# MCH_FPGA_Banks_44_45_46_DDR64.net
KiCad netlist of a schematic drawn in Altium Designer
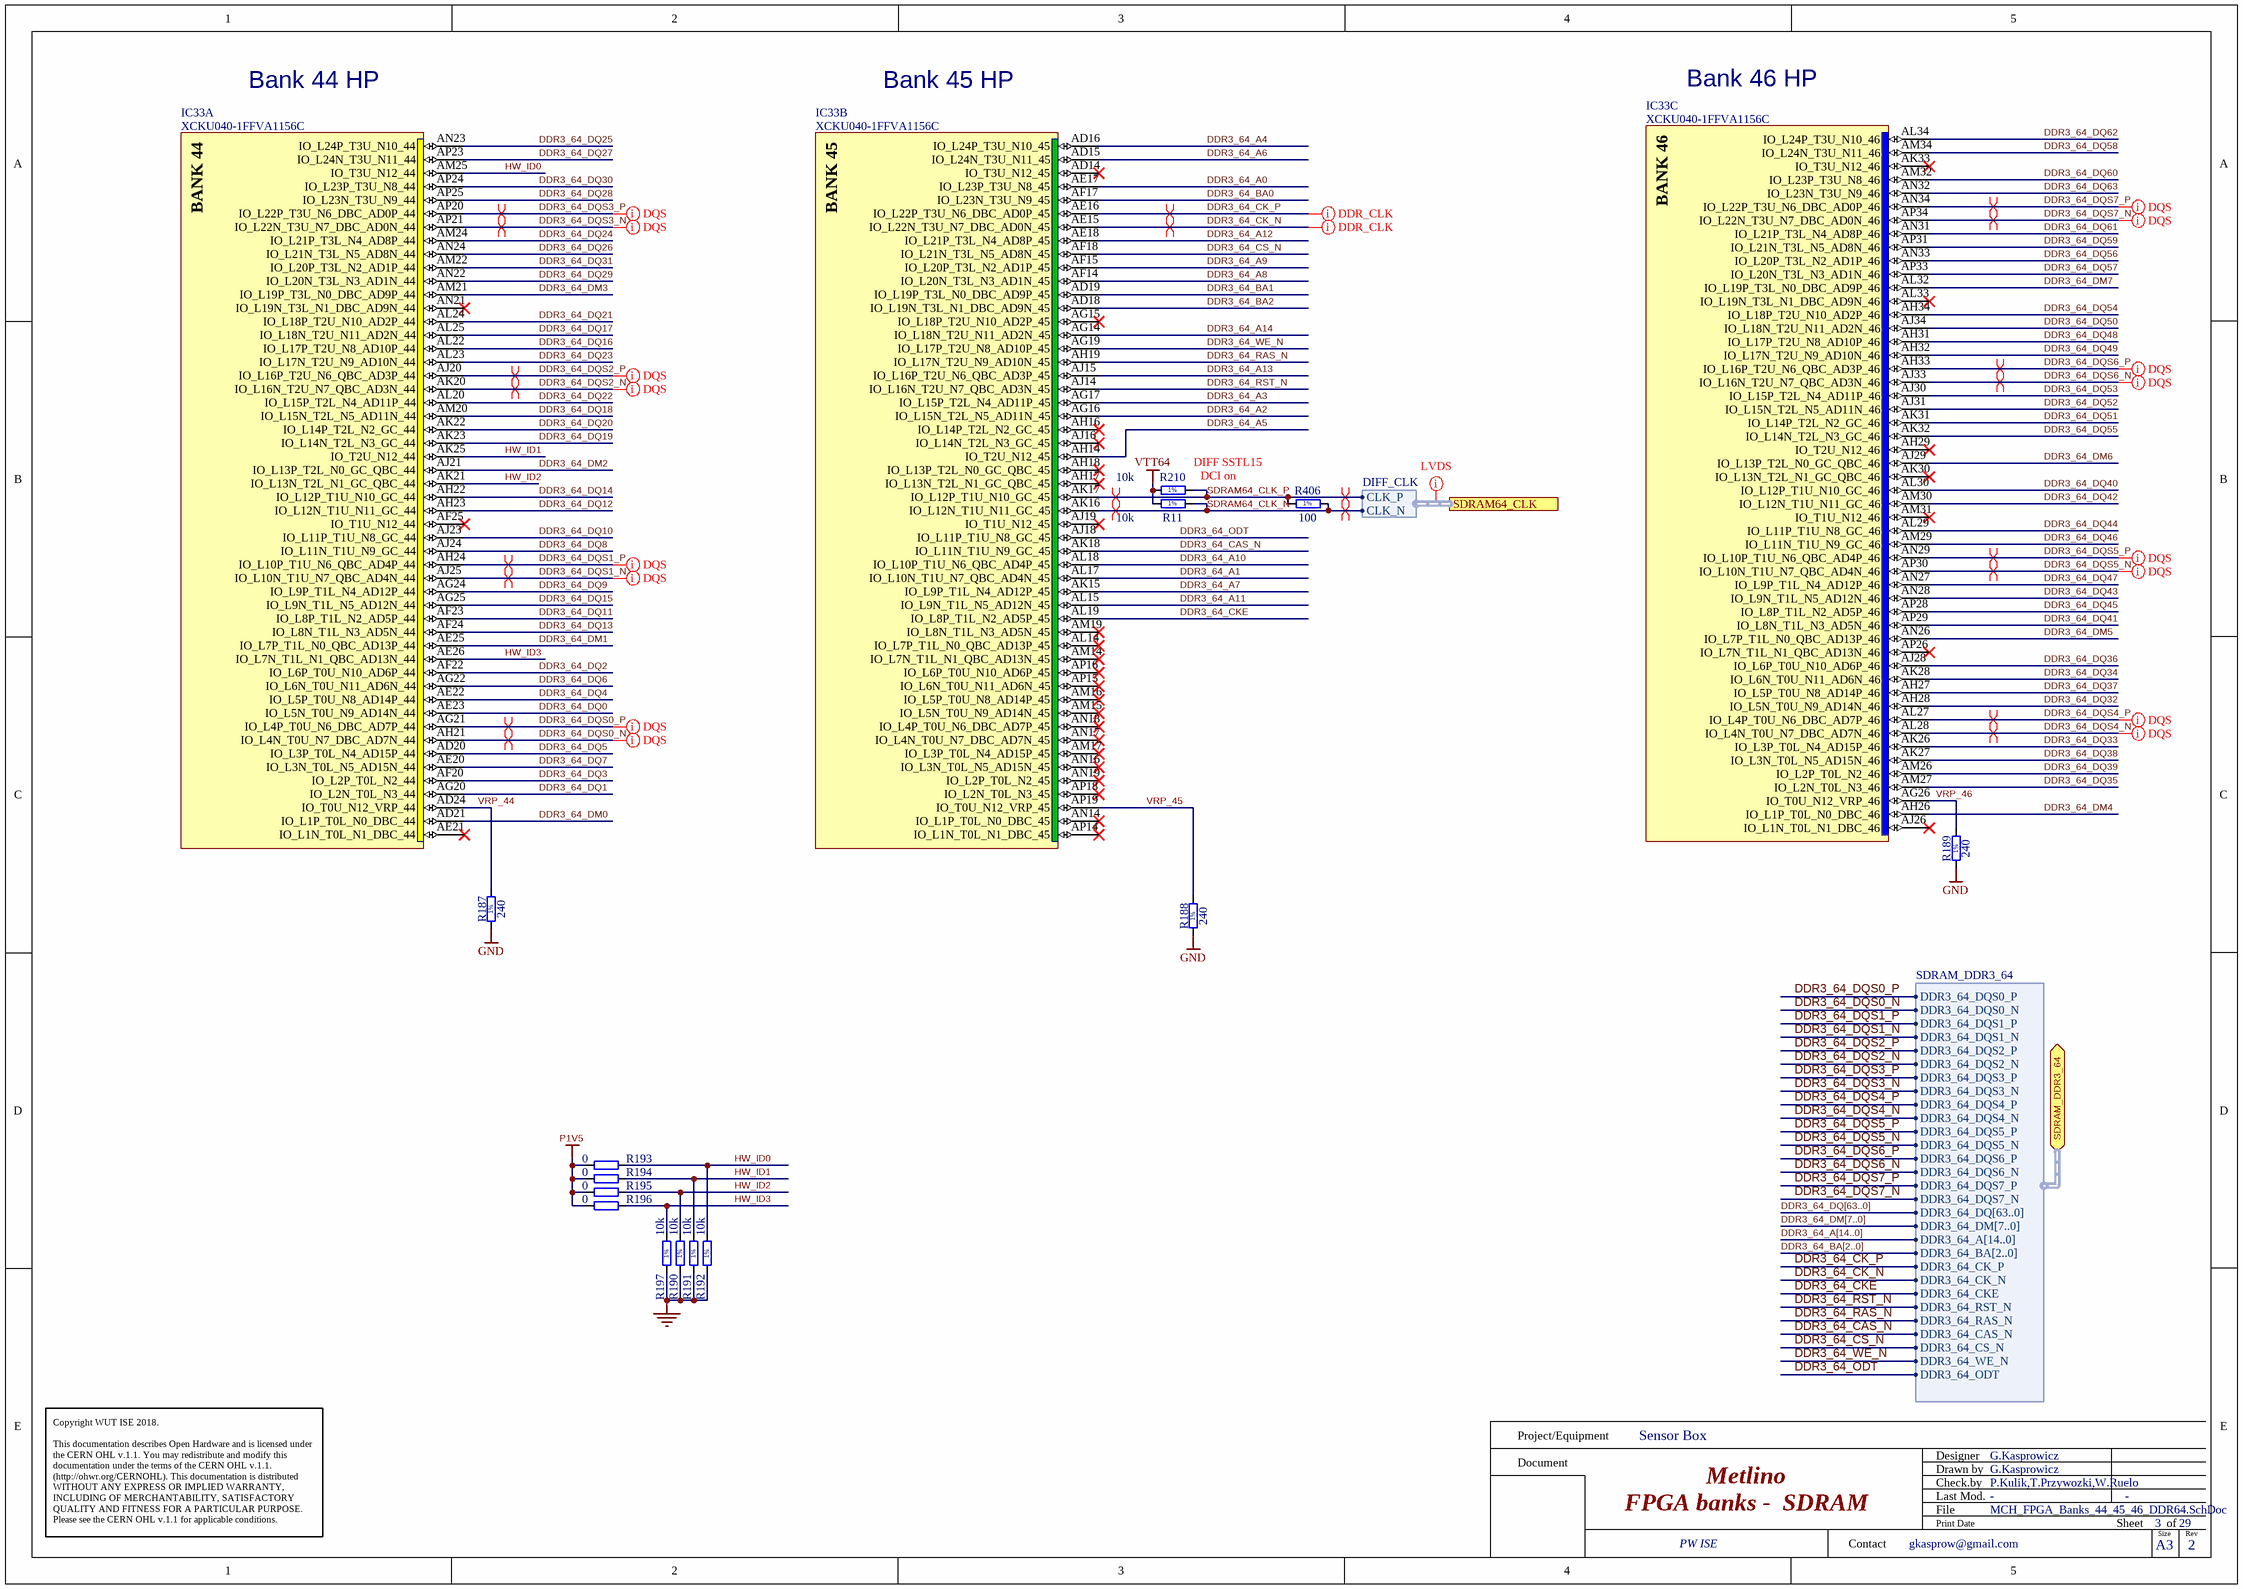
[diagram p0: MCH_FPGA_Banks_44_45_46_DDR64.SchDoc]

(export (version "E")
  (design (tool "Eeschema 10.0.6"))
  (components
    (comp (ref "IC33")
      (value "XCKU040-1FFVA1156C")
      (footprint "BGA1156C100P34X34_3500X3500X350")
      (description "Kintex UltraScale FPGA, 520 I/O, 530K Cells, 1156-Ball BGA, Speed Grade 1, Commercial Grade")
      (fields (field (name "MANUFACTURER") "XILINX") (field (name "AUTHOR") "CERN DEM CA"))
      (libsource (lib "ICs And Semiconductors") (part "XCKU040-1FFVA1156C"))
    )
    (comp (ref "R11")
      (value "10k")
      (footprint "RESC1005X40N")
      (description "Resistor - 1%")
      (fields
        (field (name "MANUFACTURER PART NUMBER") "R0402_10K_1%_0.0625W_100PPM")
        (field (name "MANUFACTURER") "GENERIC")
        (field (name "AUTHOR") "CERN DEM JLC")
      )
      (libsource (lib "Resistors") (part "Resistor - 1%"))
    )
    (comp (ref "R187")
      (value "240")
      (footprint "RESC1005X40N")
      (description "Resistor - 1%")
      (fields
        (field (name "MANUFACTURER PART NUMBER") "R0402_240R_1%_0.0625W_100PPM")
        (field (name "MANUFACTURER") "GENERIC")
        (field (name "AUTHOR") "CERN DEM JLC")
      )
      (libsource (lib "Resistors") (part "Resistor - 1%"))
    )
    (comp (ref "R188")
      (value "240")
      (footprint "RESC1005X40N")
      (description "Resistor - 1%")
      (fields
        (field (name "MANUFACTURER PART NUMBER") "R0402_240R_1%_0.0625W_100PPM")
        (field (name "MANUFACTURER") "GENERIC")
        (field (name "AUTHOR") "CERN DEM JLC")
      )
      (libsource (lib "Resistors") (part "Resistor - 1%"))
    )
    (comp (ref "R189")
      (value "240")
      (footprint "RESC1005X40N")
      (description "Resistor - 1%")
      (fields
        (field (name "MANUFACTURER PART NUMBER") "R0402_240R_1%_0.0625W_100PPM")
        (field (name "MANUFACTURER") "GENERIC")
        (field (name "AUTHOR") "CERN DEM JLC")
      )
      (libsource (lib "Resistors") (part "Resistor - 1%"))
    )
    (comp (ref "R190")
      (value "10k")
      (footprint "RESC1005X40N")
      (description "Resistor - 1%")
      (fields
        (field (name "MANUFACTURER PART NUMBER") "R0402_10K_1%_0.0625W_100PPM")
        (field (name "MANUFACTURER") "GENERIC")
        (field (name "AUTHOR") "CERN DEM JLC")
      )
      (libsource (lib "Resistors") (part "Resistor - 1%"))
    )
    (comp (ref "R191")
      (value "10k")
      (footprint "RESC1005X40N")
      (description "Resistor - 1%")
      (fields
        (field (name "MANUFACTURER PART NUMBER") "R0402_10K_1%_0.0625W_100PPM")
        (field (name "MANUFACTURER") "GENERIC")
        (field (name "AUTHOR") "CERN DEM JLC")
      )
      (libsource (lib "Resistors") (part "Resistor - 1%"))
    )
    (comp (ref "R192")
      (value "10k")
      (footprint "RESC1005X40N")
      (description "Resistor - 1%")
      (fields
        (field (name "MANUFACTURER PART NUMBER") "R0402_10K_1%_0.0625W_100PPM")
        (field (name "MANUFACTURER") "GENERIC")
        (field (name "AUTHOR") "CERN DEM JLC")
      )
      (libsource (lib "Resistors") (part "Resistor - 1%"))
    )
    (comp (ref "R193")
      (value "0")
      (footprint "RESC1005X40N")
      (description "Resistor")
      (fields
        (field (name "MANUFACTURER PART NUMBER") "R0402_0R_JUMPER")
        (field (name "MANUFACTURER") "GENERIC")
        (field (name "AUTHOR") "CERN DEM JLC")
      )
      (libsource (lib "Resistors") (part "Resistor"))
    )
    (comp (ref "R194")
      (value "0")
      (footprint "RESC1005X40N")
      (description "Resistor")
      (fields
        (field (name "MANUFACTURER PART NUMBER") "R0402_0R_JUMPER")
        (field (name "MANUFACTURER") "GENERIC")
        (field (name "AUTHOR") "CERN DEM JLC")
      )
      (libsource (lib "Resistors") (part "Resistor"))
    )
    (comp (ref "R195")
      (value "0")
      (footprint "RESC1005X40N")
      (description "Resistor")
      (fields
        (field (name "MANUFACTURER PART NUMBER") "R0402_0R_JUMPER")
        (field (name "MANUFACTURER") "GENERIC")
        (field (name "AUTHOR") "CERN DEM JLC")
      )
      (libsource (lib "Resistors") (part "Resistor"))
    )
    (comp (ref "R196")
      (value "0")
      (footprint "RESC1005X40N")
      (description "Resistor")
      (fields
        (field (name "MANUFACTURER PART NUMBER") "R0402_0R_JUMPER")
        (field (name "MANUFACTURER") "GENERIC")
        (field (name "AUTHOR") "CERN DEM JLC")
      )
      (libsource (lib "Resistors") (part "Resistor"))
    )
    (comp (ref "R197")
      (value "10k")
      (footprint "RESC1005X40N")
      (description "Resistor - 1%")
      (fields
        (field (name "MANUFACTURER PART NUMBER") "R0402_10K_1%_0.0625W_100PPM")
        (field (name "MANUFACTURER") "GENERIC")
        (field (name "AUTHOR") "CERN DEM JLC")
      )
      (libsource (lib "Resistors") (part "Resistor - 1%"))
    )
    (comp (ref "R210")
      (value "10k")
      (footprint "RESC1005X40N")
      (description "Resistor - 1%")
      (fields
        (field (name "MANUFACTURER PART NUMBER") "R0402_10K_1%_0.0625W_100PPM")
        (field (name "MANUFACTURER") "GENERIC")
        (field (name "AUTHOR") "CERN DEM JLC")
      )
      (libsource (lib "Resistors") (part "Resistor - 1%"))
    )
    (comp (ref "R406")
      (value "100")
      (footprint "RESC0603X28N")
      (description "Resistor - 1%")
      (fields
        (field (name "MANUFACTURER PART NUMBER") "R0201_100R_1%_0.05W_200PPM")
        (field (name "MANUFACTURER") "GENERIC")
        (field (name "AUTHOR") "CERN DEM JLC")
      )
      (libsource (lib "Resistors") (part "Resistor - 1%"))
    )
  )
  (nets
    (net (code "3") (name "/DDR3_64_A0") (class "Default")
      (node (ref "IC33") (pin "AE17") (pinfunction "IO_L23P_T3U_N8_45_AE17") (pintype "bidirectional"))
    )
    (net (code "4") (name "/DDR3_64_A1") (class "Default")
      (node (ref "IC33") (pin "AL17") (pinfunction "IO_L10N_T1U_N7_QBC_AD4N_45_AL17") (pintype "bidirectional"))
    )
    (net (code "5") (name "/DDR3_64_A2") (class "Default")
      (node (ref "IC33") (pin "AG16") (pinfunction "IO_L15N_T2L_N5_AD11N_45_AG16") (pintype "bidirectional"))
    )
    (net (code "6") (name "/DDR3_64_A3") (class "Default")
      (node (ref "IC33") (pin "AG17") (pinfunction "IO_L15P_T2L_N4_AD11P_45_AG17") (pintype "bidirectional"))
    )
    (net (code "7") (name "/DDR3_64_A4") (class "Default")
      (node (ref "IC33") (pin "AD16") (pinfunction "IO_L24P_T3U_N10_45_AD16") (pintype "bidirectional"))
    )
    (net (code "8") (name "/DDR3_64_A5") (class "Default")
      (node (ref "IC33") (pin "AH14") (pinfunction "IO_T2U_N12_45_AH14") (pintype "bidirectional"))
    )
    (net (code "9") (name "/DDR3_64_A6") (class "Default")
      (node (ref "IC33") (pin "AD15") (pinfunction "IO_L24N_T3U_N11_45_AD15") (pintype "bidirectional"))
    )
    (net (code "10") (name "/DDR3_64_A7") (class "Default")
      (node (ref "IC33") (pin "AK15") (pinfunction "IO_L9P_T1L_N4_AD12P_45_AK15") (pintype "bidirectional"))
    )
    (net (code "11") (name "/DDR3_64_A8") (class "Default")
      (node (ref "IC33") (pin "AF14") (pinfunction "IO_L20N_T3L_N3_AD1N_45_AF14") (pintype "bidirectional"))
    )
    (net (code "12") (name "/DDR3_64_A9") (class "Default")
      (node (ref "IC33") (pin "AF15") (pinfunction "IO_L20P_T3L_N2_AD1P_45_AF15") (pintype "bidirectional"))
    )
    (net (code "13") (name "/DDR3_64_A10") (class "Default")
      (node (ref "IC33") (pin "AL18") (pinfunction "IO_L10P_T1U_N6_QBC_AD4P_45_AL18") (pintype "bidirectional"))
    )
    (net (code "14") (name "/DDR3_64_A11") (class "Default")
      (node (ref "IC33") (pin "AL15") (pinfunction "IO_L9N_T1L_N5_AD12N_45_AL15") (pintype "bidirectional"))
    )
    (net (code "15") (name "/DDR3_64_A12") (class "Default")
      (node (ref "IC33") (pin "AE18") (pinfunction "IO_L21P_T3L_N4_AD8P_45_AE18") (pintype "bidirectional"))
    )
    (net (code "16") (name "/DDR3_64_A13") (class "Default")
      (node (ref "IC33") (pin "AJ15") (pinfunction "IO_L16P_T2U_N6_QBC_AD3P_45_AJ15") (pintype "bidirectional"))
    )
    (net (code "17") (name "/DDR3_64_A14") (class "Default")
      (node (ref "IC33") (pin "AG14") (pinfunction "IO_L18N_T2U_N11_AD2N_45_AG14") (pintype "bidirectional"))
    )
    (net (code "19") (name "/DDR3_64_BA0") (class "Default")
      (node (ref "IC33") (pin "AF17") (pinfunction "IO_L23N_T3U_N9_45_AF17") (pintype "bidirectional"))
    )
    (net (code "20") (name "/DDR3_64_BA1") (class "Default")
      (node (ref "IC33") (pin "AD19") (pinfunction "IO_L19P_T3L_N0_DBC_AD9P_45_AD19") (pintype "bidirectional"))
    )
    (net (code "21") (name "/DDR3_64_BA2") (class "Default")
      (node (ref "IC33") (pin "AD18") (pinfunction "IO_L19N_T3L_N1_DBC_AD9N_45_AD18") (pintype "bidirectional"))
    )
    (net (code "23") (name "/DDR3_64_CAS_N") (class "Default")
      (node (ref "IC33") (pin "AK18") (pinfunction "IO_L11N_T1U_N9_GC_45_AK18") (pintype "bidirectional"))
    )
    (net (code "24") (name "/DDR3_64_CKE") (class "Default")
      (node (ref "IC33") (pin "AL19") (pinfunction "IO_L8P_T1L_N2_AD5P_45_AL19") (pintype "bidirectional"))
    )
    (net (code "25") (name "/DDR3_64_CK_N") (class "Default")
      (node (ref "IC33") (pin "AE15") (pinfunction "IO_L22N_T3U_N7_DBC_AD0N_45_AE15") (pintype "bidirectional"))
    )
    (net (code "26") (name "/DDR3_64_CK_P") (class "Default")
      (node (ref "IC33") (pin "AE16") (pinfunction "IO_L22P_T3U_N6_DBC_AD0P_45_AE16") (pintype "bidirectional"))
    )
    (net (code "27") (name "/DDR3_64_CS_N") (class "Default")
      (node (ref "IC33") (pin "AF18") (pinfunction "IO_L21N_T3L_N5_AD8N_45_AF18") (pintype "bidirectional"))
    )
    (net (code "28") (name "/DDR3_64_DM0") (class "Default")
      (node (ref "IC33") (pin "AD21") (pinfunction "IO_L1P_T0L_N0_DBC_44_AD21") (pintype "bidirectional"))
    )
    (net (code "29") (name "/DDR3_64_DM1") (class "Default")
      (node (ref "IC33") (pin "AE25") (pinfunction "IO_L7P_T1L_N0_QBC_AD13P_44_AE25") (pintype "bidirectional"))
    )
    (net (code "30") (name "/DDR3_64_DM2") (class "Default")
      (node (ref "IC33") (pin "AJ21") (pinfunction "IO_L13P_T2L_N0_GC_QBC_44_AJ21") (pintype "bidirectional"))
    )
    (net (code "31") (name "/DDR3_64_DM3") (class "Default")
      (node (ref "IC33") (pin "AM21") (pinfunction "IO_L19P_T3L_N0_DBC_AD9P_44_AM21") (pintype "bidirectional"))
    )
    (net (code "32") (name "/DDR3_64_DM4") (class "Default")
      (node (ref "IC33") (pin "AH26") (pinfunction "IO_L1P_T0L_N0_DBC_46_AH26") (pintype "bidirectional"))
    )
    (net (code "33") (name "/DDR3_64_DM5") (class "Default")
      (node (ref "IC33") (pin "AN26") (pinfunction "IO_L7P_T1L_N0_QBC_AD13P_46_AN26") (pintype "bidirectional"))
    )
    (net (code "34") (name "/DDR3_64_DM6") (class "Default")
      (node (ref "IC33") (pin "AJ29") (pinfunction "IO_L13P_T2L_N0_GC_QBC_46_AJ29") (pintype "bidirectional"))
    )
    (net (code "35") (name "/DDR3_64_DM7") (class "Default")
      (node (ref "IC33") (pin "AL32") (pinfunction "IO_L19P_T3L_N0_DBC_AD9P_46_AL32") (pintype "bidirectional"))
    )
    (net (code "37") (name "/DDR3_64_DQ0") (class "Default")
      (node (ref "IC33") (pin "AE23") (pinfunction "IO_L5N_T0U_N9_AD14N_44_AE23") (pintype "bidirectional"))
    )
    (net (code "38") (name "/DDR3_64_DQ1") (class "Default")
      (node (ref "IC33") (pin "AG20") (pinfunction "IO_L2N_T0L_N3_44_AG20") (pintype "bidirectional"))
    )
    (net (code "39") (name "/DDR3_64_DQ2") (class "Default")
      (node (ref "IC33") (pin "AF22") (pinfunction "IO_L6P_T0U_N10_AD6P_44_AF22") (pintype "bidirectional"))
    )
    (net (code "40") (name "/DDR3_64_DQ3") (class "Default")
      (node (ref "IC33") (pin "AF20") (pinfunction "IO_L2P_T0L_N2_44_AF20") (pintype "bidirectional"))
    )
    (net (code "41") (name "/DDR3_64_DQ4") (class "Default")
      (node (ref "IC33") (pin "AE22") (pinfunction "IO_L5P_T0U_N8_AD14P_44_AE22") (pintype "bidirectional"))
    )
    (net (code "42") (name "/DDR3_64_DQ5") (class "Default")
      (node (ref "IC33") (pin "AD20") (pinfunction "IO_L3P_T0L_N4_AD15P_44_AD20") (pintype "bidirectional"))
    )
    (net (code "43") (name "/DDR3_64_DQ6") (class "Default")
      (node (ref "IC33") (pin "AG22") (pinfunction "IO_L6N_T0U_N11_AD6N_44_AG22") (pintype "bidirectional"))
    )
    (net (code "44") (name "/DDR3_64_DQ7") (class "Default")
      (node (ref "IC33") (pin "AE20") (pinfunction "IO_L3N_T0L_N5_AD15N_44_AE20") (pintype "bidirectional"))
    )
    (net (code "45") (name "/DDR3_64_DQ8") (class "Default")
      (node (ref "IC33") (pin "AJ24") (pinfunction "IO_L11N_T1U_N9_GC_44_AJ24") (pintype "bidirectional"))
    )
    (net (code "46") (name "/DDR3_64_DQ9") (class "Default")
      (node (ref "IC33") (pin "AG24") (pinfunction "IO_L9P_T1L_N4_AD12P_44_AG24") (pintype "bidirectional"))
    )
    (net (code "47") (name "/DDR3_64_DQ10") (class "Default")
      (node (ref "IC33") (pin "AJ23") (pinfunction "IO_L11P_T1U_N8_GC_44_AJ23") (pintype "bidirectional"))
    )
    (net (code "48") (name "/DDR3_64_DQ11") (class "Default")
      (node (ref "IC33") (pin "AF23") (pinfunction "IO_L8P_T1L_N2_AD5P_44_AF23") (pintype "bidirectional"))
    )
    (net (code "49") (name "/DDR3_64_DQ12") (class "Default")
      (node (ref "IC33") (pin "AH23") (pinfunction "IO_L12N_T1U_N11_GC_44_AH23") (pintype "bidirectional"))
    )
    (net (code "50") (name "/DDR3_64_DQ13") (class "Default")
      (node (ref "IC33") (pin "AF24") (pinfunction "IO_L8N_T1L_N3_AD5N_44_AF24") (pintype "bidirectional"))
    )
    (net (code "51") (name "/DDR3_64_DQ14") (class "Default")
      (node (ref "IC33") (pin "AH22") (pinfunction "IO_L12P_T1U_N10_GC_44_AH22") (pintype "bidirectional"))
    )
    (net (code "52") (name "/DDR3_64_DQ15") (class "Default")
      (node (ref "IC33") (pin "AG25") (pinfunction "IO_L9N_T1L_N5_AD12N_44_AG25") (pintype "bidirectional"))
    )
    (net (code "53") (name "/DDR3_64_DQ16") (class "Default")
      (node (ref "IC33") (pin "AL22") (pinfunction "IO_L17P_T2U_N8_AD10P_44_AL22") (pintype "bidirectional"))
    )
    (net (code "54") (name "/DDR3_64_DQ17") (class "Default")
      (node (ref "IC33") (pin "AL25") (pinfunction "IO_L18N_T2U_N11_AD2N_44_AL25") (pintype "bidirectional"))
    )
    (net (code "55") (name "/DDR3_64_DQ18") (class "Default")
      (node (ref "IC33") (pin "AM20") (pinfunction "IO_L15N_T2L_N5_AD11N_44_AM20") (pintype "bidirectional"))
    )
    (net (code "56") (name "/DDR3_64_DQ19") (class "Default")
      (node (ref "IC33") (pin "AK23") (pinfunction "IO_L14N_T2L_N3_GC_44_AK23") (pintype "bidirectional"))
    )
    (net (code "57") (name "/DDR3_64_DQ20") (class "Default")
      (node (ref "IC33") (pin "AK22") (pinfunction "IO_L14P_T2L_N2_GC_44_AK22") (pintype "bidirectional"))
    )
    (net (code "58") (name "/DDR3_64_DQ21") (class "Default")
      (node (ref "IC33") (pin "AL24") (pinfunction "IO_L18P_T2U_N10_AD2P_44_AL24") (pintype "bidirectional"))
    )
    (net (code "59") (name "/DDR3_64_DQ22") (class "Default")
      (node (ref "IC33") (pin "AL20") (pinfunction "IO_L15P_T2L_N4_AD11P_44_AL20") (pintype "bidirectional"))
    )
    (net (code "60") (name "/DDR3_64_DQ23") (class "Default")
      (node (ref "IC33") (pin "AL23") (pinfunction "IO_L17N_T2U_N9_AD10N_44_AL23") (pintype "bidirectional"))
    )
    (net (code "61") (name "/DDR3_64_DQ24") (class "Default")
      (node (ref "IC33") (pin "AM24") (pinfunction "IO_L21P_T3L_N4_AD8P_44_AM24") (pintype "bidirectional"))
    )
    (net (code "62") (name "/DDR3_64_DQ25") (class "Default")
      (node (ref "IC33") (pin "AN23") (pinfunction "IO_L24P_T3U_N10_44_AN23") (pintype "bidirectional"))
    )
    (net (code "63") (name "/DDR3_64_DQ26") (class "Default")
      (node (ref "IC33") (pin "AN24") (pinfunction "IO_L21N_T3L_N5_AD8N_44_AN24") (pintype "bidirectional"))
    )
    (net (code "64") (name "/DDR3_64_DQ27") (class "Default")
      (node (ref "IC33") (pin "AP23") (pinfunction "IO_L24N_T3U_N11_44_AP23") (pintype "bidirectional"))
    )
    (net (code "65") (name "/DDR3_64_DQ28") (class "Default")
      (node (ref "IC33") (pin "AP25") (pinfunction "IO_L23N_T3U_N9_44_AP25") (pintype "bidirectional"))
    )
    (net (code "66") (name "/DDR3_64_DQ29") (class "Default")
      (node (ref "IC33") (pin "AN22") (pinfunction "IO_L20N_T3L_N3_AD1N_44_AN22") (pintype "bidirectional"))
    )
    (net (code "67") (name "/DDR3_64_DQ30") (class "Default")
      (node (ref "IC33") (pin "AP24") (pinfunction "IO_L23P_T3U_N8_44_AP24") (pintype "bidirectional"))
    )
    (net (code "68") (name "/DDR3_64_DQ31") (class "Default")
      (node (ref "IC33") (pin "AM22") (pinfunction "IO_L20P_T3L_N2_AD1P_44_AM22") (pintype "bidirectional"))
    )
    (net (code "69") (name "/DDR3_64_DQ32") (class "Default")
      (node (ref "IC33") (pin "AH28") (pinfunction "IO_L5N_T0U_N9_AD14N_46_AH28") (pintype "bidirectional"))
    )
    (net (code "70") (name "/DDR3_64_DQ33") (class "Default")
      (node (ref "IC33") (pin "AK26") (pinfunction "IO_L3P_T0L_N4_AD15P_46_AK26") (pintype "bidirectional"))
    )
    (net (code "71") (name "/DDR3_64_DQ34") (class "Default")
      (node (ref "IC33") (pin "AK28") (pinfunction "IO_L6N_T0U_N11_AD6N_46_AK28") (pintype "bidirectional"))
    )
    (net (code "72") (name "/DDR3_64_DQ35") (class "Default")
      (node (ref "IC33") (pin "AM27") (pinfunction "IO_L2N_T0L_N3_46_AM27") (pintype "bidirectional"))
    )
    (net (code "73") (name "/DDR3_64_DQ36") (class "Default")
      (node (ref "IC33") (pin "AJ28") (pinfunction "IO_L6P_T0U_N10_AD6P_46_AJ28") (pintype "bidirectional"))
    )
    (net (code "74") (name "/DDR3_64_DQ37") (class "Default")
      (node (ref "IC33") (pin "AH27") (pinfunction "IO_L5P_T0U_N8_AD14P_46_AH27") (pintype "bidirectional"))
    )
    (net (code "75") (name "/DDR3_64_DQ38") (class "Default")
      (node (ref "IC33") (pin "AK27") (pinfunction "IO_L3N_T0L_N5_AD15N_46_AK27") (pintype "bidirectional"))
    )
    (net (code "76") (name "/DDR3_64_DQ39") (class "Default")
      (node (ref "IC33") (pin "AM26") (pinfunction "IO_L2P_T0L_N2_46_AM26") (pintype "bidirectional"))
    )
    (net (code "77") (name "/DDR3_64_DQ40") (class "Default")
      (node (ref "IC33") (pin "AL30") (pinfunction "IO_L12P_T1U_N10_GC_46_AL30") (pintype "bidirectional"))
    )
    (net (code "78") (name "/DDR3_64_DQ41") (class "Default")
      (node (ref "IC33") (pin "AP29") (pinfunction "IO_L8N_T1L_N3_AD5N_46_AP29") (pintype "bidirectional"))
    )
    (net (code "79") (name "/DDR3_64_DQ42") (class "Default")
      (node (ref "IC33") (pin "AM30") (pinfunction "IO_L12N_T1U_N11_GC_46_AM30") (pintype "bidirectional"))
    )
    (net (code "80") (name "/DDR3_64_DQ43") (class "Default")
      (node (ref "IC33") (pin "AN28") (pinfunction "IO_L9N_T1L_N5_AD12N_46_AN28") (pintype "bidirectional"))
    )
    (net (code "81") (name "/DDR3_64_DQ44") (class "Default")
      (node (ref "IC33") (pin "AL29") (pinfunction "IO_L11P_T1U_N8_GC_46_AL29") (pintype "bidirectional"))
    )
    (net (code "82") (name "/DDR3_64_DQ45") (class "Default")
      (node (ref "IC33") (pin "AP28") (pinfunction "IO_L8P_T1L_N2_AD5P_46_AP28") (pintype "bidirectional"))
    )
    (net (code "83") (name "/DDR3_64_DQ46") (class "Default")
      (node (ref "IC33") (pin "AM29") (pinfunction "IO_L11N_T1U_N9_GC_46_AM29") (pintype "bidirectional"))
    )
    (net (code "84") (name "/DDR3_64_DQ47") (class "Default")
      (node (ref "IC33") (pin "AN27") (pinfunction "IO_L9P_T1L_N4_AD12P_46_AN27") (pintype "bidirectional"))
    )
    (net (code "85") (name "/DDR3_64_DQ48") (class "Default")
      (node (ref "IC33") (pin "AH31") (pinfunction "IO_L17P_T2U_N8_AD10P_46_AH31") (pintype "bidirectional"))
    )
    (net (code "86") (name "/DDR3_64_DQ49") (class "Default")
      (node (ref "IC33") (pin "AH32") (pinfunction "IO_L17N_T2U_N9_AD10N_46_AH32") (pintype "bidirectional"))
    )
    (net (code "87") (name "/DDR3_64_DQ50") (class "Default")
      (node (ref "IC33") (pin "AJ34") (pinfunction "IO_L18N_T2U_N11_AD2N_46_AJ34") (pintype "bidirectional"))
    )
    (net (code "88") (name "/DDR3_64_DQ51") (class "Default")
      (node (ref "IC33") (pin "AK31") (pinfunction "IO_L14P_T2L_N2_GC_46_AK31") (pintype "bidirectional"))
    )
    (net (code "89") (name "/DDR3_64_DQ52") (class "Default")
      (node (ref "IC33") (pin "AJ31") (pinfunction "IO_L15N_T2L_N5_AD11N_46_AJ31") (pintype "bidirectional"))
    )
    (net (code "90") (name "/DDR3_64_DQ53") (class "Default")
      (node (ref "IC33") (pin "AJ30") (pinfunction "IO_L15P_T2L_N4_AD11P_46_AJ30") (pintype "bidirectional"))
    )
    (net (code "91") (name "/DDR3_64_DQ54") (class "Default")
      (node (ref "IC33") (pin "AH34") (pinfunction "IO_L18P_T2U_N10_AD2P_46_AH34") (pintype "bidirectional"))
    )
    (net (code "92") (name "/DDR3_64_DQ55") (class "Default")
      (node (ref "IC33") (pin "AK32") (pinfunction "IO_L14N_T2L_N3_GC_46_AK32") (pintype "bidirectional"))
    )
    (net (code "93") (name "/DDR3_64_DQ56") (class "Default")
      (node (ref "IC33") (pin "AN33") (pinfunction "IO_L20P_T3L_N2_AD1P_46_AN33") (pintype "bidirectional"))
    )
    (net (code "94") (name "/DDR3_64_DQ57") (class "Default")
      (node (ref "IC33") (pin "AP33") (pinfunction "IO_L20N_T3L_N3_AD1N_46_AP33") (pintype "bidirectional"))
    )
    (net (code "95") (name "/DDR3_64_DQ58") (class "Default")
      (node (ref "IC33") (pin "AM34") (pinfunction "IO_L24N_T3U_N11_46_AM34") (pintype "bidirectional"))
    )
    (net (code "96") (name "/DDR3_64_DQ59") (class "Default")
      (node (ref "IC33") (pin "AP31") (pinfunction "IO_L21N_T3L_N5_AD8N_46_AP31") (pintype "bidirectional"))
    )
    (net (code "97") (name "/DDR3_64_DQ60") (class "Default")
      (node (ref "IC33") (pin "AM32") (pinfunction "IO_L23P_T3U_N8_46_AM32") (pintype "bidirectional"))
    )
    (net (code "98") (name "/DDR3_64_DQ61") (class "Default")
      (node (ref "IC33") (pin "AN31") (pinfunction "IO_L21P_T3L_N4_AD8P_46_AN31") (pintype "bidirectional"))
    )
    (net (code "99") (name "/DDR3_64_DQ62") (class "Default")
      (node (ref "IC33") (pin "AL34") (pinfunction "IO_L24P_T3U_N10_46_AL34") (pintype "bidirectional"))
    )
    (net (code "100") (name "/DDR3_64_DQ63") (class "Default")
      (node (ref "IC33") (pin "AN32") (pinfunction "IO_L23N_T3U_N9_46_AN32") (pintype "bidirectional"))
    )
    (net (code "101") (name "/DDR3_64_DQS0_N") (class "Default")
      (node (ref "IC33") (pin "AH21") (pinfunction "IO_L4N_T0U_N7_DBC_AD7N_44_AH21") (pintype "bidirectional"))
    )
    (net (code "102") (name "/DDR3_64_DQS0_P") (class "Default")
      (node (ref "IC33") (pin "AG21") (pinfunction "IO_L4P_T0U_N6_DBC_AD7P_44_AG21") (pintype "bidirectional"))
    )
    (net (code "103") (name "/DDR3_64_DQS1_N") (class "Default")
      (node (ref "IC33") (pin "AJ25") (pinfunction "IO_L10N_T1U_N7_QBC_AD4N_44_AJ25") (pintype "bidirectional"))
    )
    (net (code "104") (name "/DDR3_64_DQS1_P") (class "Default")
      (node (ref "IC33") (pin "AH24") (pinfunction "IO_L10P_T1U_N6_QBC_AD4P_44_AH24") (pintype "bidirectional"))
    )
    (net (code "105") (name "/DDR3_64_DQS2_N") (class "Default")
      (node (ref "IC33") (pin "AK20") (pinfunction "IO_L16N_T2U_N7_QBC_AD3N_44_AK20") (pintype "bidirectional"))
    )
    (net (code "106") (name "/DDR3_64_DQS2_P") (class "Default")
      (node (ref "IC33") (pin "AJ20") (pinfunction "IO_L16P_T2U_N6_QBC_AD3P_44_AJ20") (pintype "bidirectional"))
    )
    (net (code "107") (name "/DDR3_64_DQS3_N") (class "Default")
      (node (ref "IC33") (pin "AP21") (pinfunction "IO_L22N_T3U_N7_DBC_AD0N_44_AP21") (pintype "bidirectional"))
    )
    (net (code "108") (name "/DDR3_64_DQS3_P") (class "Default")
      (node (ref "IC33") (pin "AP20") (pinfunction "IO_L22P_T3U_N6_DBC_AD0P_44_AP20") (pintype "bidirectional"))
    )
    (net (code "109") (name "/DDR3_64_DQS4_N") (class "Default")
      (node (ref "IC33") (pin "AL28") (pinfunction "IO_L4N_T0U_N7_DBC_AD7N_46_AL28") (pintype "bidirectional"))
    )
    (net (code "110") (name "/DDR3_64_DQS4_P") (class "Default")
      (node (ref "IC33") (pin "AL27") (pinfunction "IO_L4P_T0U_N6_DBC_AD7P_46_AL27") (pintype "bidirectional"))
    )
    (net (code "111") (name "/DDR3_64_DQS5_N") (class "Default")
      (node (ref "IC33") (pin "AP30") (pinfunction "IO_L10N_T1U_N7_QBC_AD4N_46_AP30") (pintype "bidirectional"))
    )
    (net (code "112") (name "/DDR3_64_DQS5_P") (class "Default")
      (node (ref "IC33") (pin "AN29") (pinfunction "IO_L10P_T1U_N6_QBC_AD4P_46_AN29") (pintype "bidirectional"))
    )
    (net (code "113") (name "/DDR3_64_DQS6_N") (class "Default")
      (node (ref "IC33") (pin "AJ33") (pinfunction "IO_L16N_T2U_N7_QBC_AD3N_46_AJ33") (pintype "bidirectional"))
    )
    (net (code "114") (name "/DDR3_64_DQS6_P") (class "Default")
      (node (ref "IC33") (pin "AH33") (pinfunction "IO_L16P_T2U_N6_QBC_AD3P_46_AH33") (pintype "bidirectional"))
    )
    (net (code "115") (name "/DDR3_64_DQS7_N") (class "Default")
      (node (ref "IC33") (pin "AP34") (pinfunction "IO_L22N_T3U_N7_DBC_AD0N_46_AP34") (pintype "bidirectional"))
    )
    (net (code "116") (name "/DDR3_64_DQS7_P") (class "Default")
      (node (ref "IC33") (pin "AN34") (pinfunction "IO_L22P_T3U_N6_DBC_AD0P_46_AN34") (pintype "bidirectional"))
    )
    (net (code "117") (name "/DDR3_64_ODT") (class "Default")
      (node (ref "IC33") (pin "AJ18") (pinfunction "IO_L11P_T1U_N8_GC_45_AJ18") (pintype "bidirectional"))
    )
    (net (code "118") (name "/DDR3_64_RAS_N") (class "Default")
      (node (ref "IC33") (pin "AH19") (pinfunction "IO_L17N_T2U_N9_AD10N_45_AH19") (pintype "bidirectional"))
    )
    (net (code "119") (name "/DDR3_64_RST_N") (class "Default")
      (node (ref "IC33") (pin "AJ14") (pinfunction "IO_L16N_T2U_N7_QBC_AD3N_45_AJ14") (pintype "bidirectional"))
    )
    (net (code "120") (name "/DDR3_64_WE_N") (class "Default")
      (node (ref "IC33") (pin "AG19") (pinfunction "IO_L17P_T2U_N8_AD10P_45_AG19") (pintype "bidirectional"))
    )
    (net (code "121") (name "/HW_ID0") (class "Default")
      (node (ref "IC33") (pin "AM25") (pinfunction "IO_T3U_N12_44_AM25") (pintype "bidirectional"))
      (node (ref "R192") (pin "2") (pinfunction "2_2") (pintype "passive"))
      (node (ref "R193") (pin "2") (pinfunction "2_2") (pintype "passive"))
    )
    (net (code "122") (name "/HW_ID1") (class "Default")
      (node (ref "IC33") (pin "AK25") (pinfunction "IO_T2U_N12_44_AK25") (pintype "bidirectional"))
      (node (ref "R191") (pin "2") (pinfunction "2_2") (pintype "passive"))
      (node (ref "R194") (pin "2") (pinfunction "2_2") (pintype "passive"))
    )
    (net (code "123") (name "/HW_ID2") (class "Default")
      (node (ref "IC33") (pin "AK21") (pinfunction "IO_L13N_T2L_N1_GC_QBC_44_AK21") (pintype "bidirectional"))
      (node (ref "R190") (pin "2") (pinfunction "2_2") (pintype "passive"))
      (node (ref "R195") (pin "2") (pinfunction "2_2") (pintype "passive"))
    )
    (net (code "124") (name "/HW_ID3") (class "Default")
      (node (ref "IC33") (pin "AE26") (pinfunction "IO_L7N_T1L_N1_QBC_AD13N_44_AE26") (pintype "bidirectional"))
      (node (ref "R196") (pin "2") (pinfunction "2_2") (pintype "passive"))
      (node (ref "R197") (pin "2") (pinfunction "2_2") (pintype "passive"))
    )
    (net (code "125") (name "/SDRAM64_CLK_N") (class "Default")
      (node (ref "IC33") (pin "AK16") (pinfunction "IO_L12N_T1U_N11_GC_45_AK16") (pintype "bidirectional"))
      (node (ref "R11") (pin "2") (pinfunction "2_2") (pintype "passive"))
      (node (ref "R406") (pin "2") (pinfunction "2_2") (pintype "passive"))
    )
    (net (code "126") (name "/SDRAM64_CLK_P") (class "Default")
      (node (ref "IC33") (pin "AK17") (pinfunction "IO_L12P_T1U_N10_GC_45_AK17") (pintype "bidirectional"))
      (node (ref "R210") (pin "2") (pinfunction "2_2") (pintype "passive"))
      (node (ref "R406") (pin "1") (pinfunction "1_1") (pintype "passive"))
    )
    (net (code "128") (name "/VRP_44") (class "Default")
      (node (ref "IC33") (pin "AD24") (pinfunction "IO_T0U_N12_VRP_44_AD24") (pintype "bidirectional"))
      (node (ref "R187") (pin "2") (pinfunction "2_2") (pintype "passive"))
    )
    (net (code "129") (name "/VRP_45") (class "Default")
      (node (ref "IC33") (pin "AP19") (pinfunction "IO_T0U_N12_VRP_45_AP19") (pintype "bidirectional"))
      (node (ref "R188") (pin "2") (pinfunction "2_2") (pintype "passive"))
    )
    (net (code "130") (name "/VRP_46") (class "Default")
      (node (ref "IC33") (pin "AG26") (pinfunction "IO_T0U_N12_VRP_46_AG26") (pintype "bidirectional"))
      (node (ref "R189") (pin "2") (pinfunction "2_2") (pintype "passive"))
    )
    (net (code "133") (name "GND") (class "Default")
      (node (ref "R187") (pin "1") (pinfunction "1_1") (pintype "passive"))
      (node (ref "R188") (pin "1") (pinfunction "1_1") (pintype "passive"))
      (node (ref "R189") (pin "1") (pinfunction "1_1") (pintype "passive"))
      (node (ref "R190") (pin "1") (pinfunction "1_1") (pintype "passive"))
      (node (ref "R191") (pin "1") (pinfunction "1_1") (pintype "passive"))
      (node (ref "R192") (pin "1") (pinfunction "1_1") (pintype "passive"))
      (node (ref "R197") (pin "1") (pinfunction "1_1") (pintype "passive"))
    )
    (net (code "134") (name "P1V5") (class "Default")
      (node (ref "R193") (pin "1") (pinfunction "1_1") (pintype "passive"))
      (node (ref "R194") (pin "1") (pinfunction "1_1") (pintype "passive"))
      (node (ref "R195") (pin "1") (pinfunction "1_1") (pintype "passive"))
      (node (ref "R196") (pin "1") (pinfunction "1_1") (pintype "passive"))
    )
    (net (code "135") (name "VTT64") (class "Default")
      (node (ref "R11") (pin "1") (pinfunction "1_1") (pintype "passive"))
      (node (ref "R210") (pin "1") (pinfunction "1_1") (pintype "passive"))
    )
    (net (code "136") (name "unconnected-(IC33A-IO_L1N_T0L_N1_DBC_44-PadAE21)") (class "Default")
      (node (ref "IC33") (pin "AE21") (pinfunction "IO_L1N_T0L_N1_DBC_44_AE21") (pintype "bidirectional+no_connect"))
    )
    (net (code "137") (name "unconnected-(IC33A-IO_L19N_T3L_N1_DBC_AD9N_44-PadAN21)") (class "Default")
      (node (ref "IC33") (pin "AN21") (pinfunction "IO_L19N_T3L_N1_DBC_AD9N_44_AN21") (pintype "bidirectional+no_connect"))
    )
    (net (code "138") (name "unconnected-(IC33A-IO_T1U_N12_44-PadAF25)") (class "Default")
      (node (ref "IC33") (pin "AF25") (pinfunction "IO_T1U_N12_44_AF25") (pintype "bidirectional+no_connect"))
    )
    (net (code "139") (name "unconnected-(IC33B-IO_L1N_T0L_N1_DBC_45-PadAP14)") (class "Default")
      (node (ref "IC33") (pin "AP14") (pinfunction "IO_L1N_T0L_N1_DBC_45_AP14") (pintype "bidirectional+no_connect"))
    )
    (net (code "140") (name "unconnected-(IC33B-IO_L1P_T0L_N0_DBC_45-PadAN14)") (class "Default")
      (node (ref "IC33") (pin "AN14") (pinfunction "IO_L1P_T0L_N0_DBC_45_AN14") (pintype "bidirectional+no_connect"))
    )
    (net (code "141") (name "unconnected-(IC33B-IO_L2N_T0L_N3_45-PadAP18)") (class "Default")
      (node (ref "IC33") (pin "AP18") (pinfunction "IO_L2N_T0L_N3_45_AP18") (pintype "bidirectional+no_connect"))
    )
    (net (code "142") (name "unconnected-(IC33B-IO_L2P_T0L_N2_45-PadAN19)") (class "Default")
      (node (ref "IC33") (pin "AN19") (pinfunction "IO_L2P_T0L_N2_45_AN19") (pintype "bidirectional+no_connect"))
    )
    (net (code "143") (name "unconnected-(IC33B-IO_L3N_T0L_N5_AD15N_45-PadAN16)") (class "Default")
      (node (ref "IC33") (pin "AN16") (pinfunction "IO_L3N_T0L_N5_AD15N_45_AN16") (pintype "bidirectional+no_connect"))
    )
    (net (code "144") (name "unconnected-(IC33B-IO_L3P_T0L_N4_AD15P_45-PadAM17)") (class "Default")
      (node (ref "IC33") (pin "AM17") (pinfunction "IO_L3P_T0L_N4_AD15P_45_AM17") (pintype "bidirectional+no_connect"))
    )
    (net (code "145") (name "unconnected-(IC33B-IO_L4N_T0U_N7_DBC_AD7N_45-PadAN17)") (class "Default")
      (node (ref "IC33") (pin "AN17") (pinfunction "IO_L4N_T0U_N7_DBC_AD7N_45_AN17") (pintype "bidirectional+no_connect"))
    )
    (net (code "146") (name "unconnected-(IC33B-IO_L4P_T0U_N6_DBC_AD7P_45-PadAN18)") (class "Default")
      (node (ref "IC33") (pin "AN18") (pinfunction "IO_L4P_T0U_N6_DBC_AD7P_45_AN18") (pintype "bidirectional+no_connect"))
    )
    (net (code "147") (name "unconnected-(IC33B-IO_L5N_T0U_N9_AD14N_45-PadAM15)") (class "Default")
      (node (ref "IC33") (pin "AM15") (pinfunction "IO_L5N_T0U_N9_AD14N_45_AM15") (pintype "bidirectional+no_connect"))
    )
    (net (code "148") (name "unconnected-(IC33B-IO_L5P_T0U_N8_AD14P_45-PadAM16)") (class "Default")
      (node (ref "IC33") (pin "AM16") (pinfunction "IO_L5P_T0U_N8_AD14P_45_AM16") (pintype "bidirectional+no_connect"))
    )
    (net (code "149") (name "unconnected-(IC33B-IO_L6N_T0U_N11_AD6N_45-PadAP15)") (class "Default")
      (node (ref "IC33") (pin "AP15") (pinfunction "IO_L6N_T0U_N11_AD6N_45_AP15") (pintype "bidirectional+no_connect"))
    )
    (net (code "150") (name "unconnected-(IC33B-IO_L6P_T0U_N10_AD6P_45-PadAP16)") (class "Default")
      (node (ref "IC33") (pin "AP16") (pinfunction "IO_L6P_T0U_N10_AD6P_45_AP16") (pintype "bidirectional+no_connect"))
    )
    (net (code "151") (name "unconnected-(IC33B-IO_L7N_T1L_N1_QBC_AD13N_45-PadAM14)") (class "Default")
      (node (ref "IC33") (pin "AM14") (pinfunction "IO_L7N_T1L_N1_QBC_AD13N_45_AM14") (pintype "bidirectional+no_connect"))
    )
    (net (code "152") (name "unconnected-(IC33B-IO_L7P_T1L_N0_QBC_AD13P_45-PadAL14)") (class "Default")
      (node (ref "IC33") (pin "AL14") (pinfunction "IO_L7P_T1L_N0_QBC_AD13P_45_AL14") (pintype "bidirectional+no_connect"))
    )
    (net (code "153") (name "unconnected-(IC33B-IO_L8N_T1L_N3_AD5N_45-PadAM19)") (class "Default")
      (node (ref "IC33") (pin "AM19") (pinfunction "IO_L8N_T1L_N3_AD5N_45_AM19") (pintype "bidirectional+no_connect"))
    )
    (net (code "154") (name "unconnected-(IC33B-IO_L13N_T2L_N1_GC_QBC_45-PadAH17)") (class "Default")
      (node (ref "IC33") (pin "AH17") (pinfunction "IO_L13N_T2L_N1_GC_QBC_45_AH17") (pintype "bidirectional+no_connect"))
    )
    (net (code "155") (name "unconnected-(IC33B-IO_L13P_T2L_N0_GC_QBC_45-PadAH18)") (class "Default")
      (node (ref "IC33") (pin "AH18") (pinfunction "IO_L13P_T2L_N0_GC_QBC_45_AH18") (pintype "bidirectional+no_connect"))
    )
    (net (code "156") (name "unconnected-(IC33B-IO_L14N_T2L_N3_GC_45-PadAJ16)") (class "Default")
      (node (ref "IC33") (pin "AJ16") (pinfunction "IO_L14N_T2L_N3_GC_45_AJ16") (pintype "bidirectional+no_connect"))
    )
    (net (code "157") (name "unconnected-(IC33B-IO_L14P_T2L_N2_GC_45-PadAH16)") (class "Default")
      (node (ref "IC33") (pin "AH16") (pinfunction "IO_L14P_T2L_N2_GC_45_AH16") (pintype "bidirectional+no_connect"))
    )
    (net (code "158") (name "unconnected-(IC33B-IO_L18P_T2U_N10_AD2P_45-PadAG15)") (class "Default")
      (node (ref "IC33") (pin "AG15") (pinfunction "IO_L18P_T2U_N10_AD2P_45_AG15") (pintype "bidirectional+no_connect"))
    )
    (net (code "159") (name "unconnected-(IC33B-IO_T1U_N12_45-PadAJ19)") (class "Default")
      (node (ref "IC33") (pin "AJ19") (pinfunction "IO_T1U_N12_45_AJ19") (pintype "bidirectional+no_connect"))
    )
    (net (code "160") (name "unconnected-(IC33B-IO_T3U_N12_45-PadAD14)") (class "Default")
      (node (ref "IC33") (pin "AD14") (pinfunction "IO_T3U_N12_45_AD14") (pintype "bidirectional+no_connect"))
    )
    (net (code "161") (name "unconnected-(IC33C-IO_L1N_T0L_N1_DBC_46-PadAJ26)") (class "Default")
      (node (ref "IC33") (pin "AJ26") (pinfunction "IO_L1N_T0L_N1_DBC_46_AJ26") (pintype "bidirectional+no_connect"))
    )
    (net (code "162") (name "unconnected-(IC33C-IO_L7N_T1L_N1_QBC_AD13N_46-PadAP26)") (class "Default")
      (node (ref "IC33") (pin "AP26") (pinfunction "IO_L7N_T1L_N1_QBC_AD13N_46_AP26") (pintype "bidirectional+no_connect"))
    )
    (net (code "163") (name "unconnected-(IC33C-IO_L13N_T2L_N1_GC_QBC_46-PadAK30)") (class "Default")
      (node (ref "IC33") (pin "AK30") (pinfunction "IO_L13N_T2L_N1_GC_QBC_46_AK30") (pintype "bidirectional+no_connect"))
    )
    (net (code "164") (name "unconnected-(IC33C-IO_L19N_T3L_N1_DBC_AD9N_46-PadAL33)") (class "Default")
      (node (ref "IC33") (pin "AL33") (pinfunction "IO_L19N_T3L_N1_DBC_AD9N_46_AL33") (pintype "bidirectional+no_connect"))
    )
    (net (code "165") (name "unconnected-(IC33C-IO_T1U_N12_46-PadAM31)") (class "Default")
      (node (ref "IC33") (pin "AM31") (pinfunction "IO_T1U_N12_46_AM31") (pintype "bidirectional+no_connect"))
    )
    (net (code "166") (name "unconnected-(IC33C-IO_T2U_N12_46-PadAH29)") (class "Default")
      (node (ref "IC33") (pin "AH29") (pinfunction "IO_T2U_N12_46_AH29") (pintype "bidirectional+no_connect"))
    )
    (net (code "167") (name "unconnected-(IC33C-IO_T3U_N12_46-PadAK33)") (class "Default")
      (node (ref "IC33") (pin "AK33") (pinfunction "IO_T3U_N12_46_AK33") (pintype "bidirectional+no_connect"))
    )
  )
)
